# testSensor.net
KiCad netlist of a schematic drawn in Altium Designer
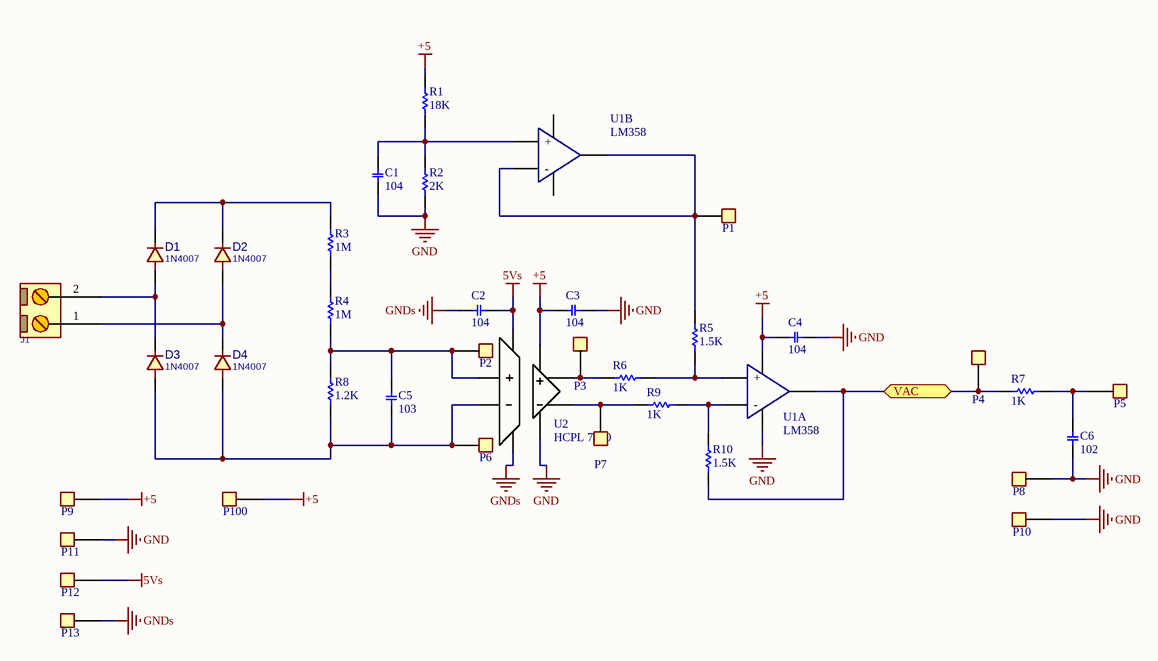
[diagram p0: testSensor.SchDoc]

(export (version "E")
  (design (tool "Eeschema 10.0.6"))
  (components
    (comp (ref "C1")
      (value "104")
      (footprint "CAP 104")
      (description "CAP Keo")
      (fields (field (name "COPYRIGHT") "VanDungEvn"))
      (libsource (lib "IoT") (part "CAP Keo"))
    )
    (comp (ref "C2")
      (value "104")
      (footprint "CAP 104")
      (description "CAP Keo")
      (fields (field (name "COPYRIGHT") "VanDungEvn"))
      (libsource (lib "IoT") (part "CAP Keo"))
    )
    (comp (ref "C3")
      (value "104")
      (footprint "CAP 104")
      (description "CAP Keo")
      (fields (field (name "COPYRIGHT") "VanDungEvn"))
      (libsource (lib "IoT") (part "CAP Keo"))
    )
    (comp (ref "C4")
      (value "104")
      (footprint "CAP 104")
      (description "CAP Keo")
      (fields (field (name "COPYRIGHT") "VanDungEvn"))
      (libsource (lib "IoT") (part "CAP Keo"))
    )
    (comp (ref "C5")
      (value "103")
      (footprint "CAP 104")
      (description "CAP Keo")
      (fields (field (name "COPYRIGHT") "VanDungEvn"))
      (libsource (lib "IoT") (part "CAP Keo"))
    )
    (comp (ref "C6")
      (value "102")
      (footprint "CAP 104")
      (description "CAP Keo")
      (fields (field (name "COPYRIGHT") "VanDungEvn"))
      (libsource (lib "IoT") (part "CAP Keo"))
    )
    (comp (ref "D1")
      (value "1N4007")
      (footprint "1N4007")
      (description "DIODE DIP")
      (fields (field (name "MANF") "Kingtronics") (field (name "MANF_P#") "M7"))
      (libsource (lib "IoT") (part "DIODE DIP"))
    )
    (comp (ref "D2")
      (value "1N4007")
      (footprint "1N4007")
      (description "DIODE DIP")
      (fields (field (name "MANF") "Kingtronics") (field (name "MANF_P#") "M7"))
      (libsource (lib "IoT") (part "DIODE DIP"))
    )
    (comp (ref "D3")
      (value "1N4007")
      (footprint "1N4007")
      (description "DIODE DIP")
      (fields (field (name "MANF") "Kingtronics") (field (name "MANF_P#") "M7"))
      (libsource (lib "IoT") (part "DIODE DIP"))
    )
    (comp (ref "D4")
      (value "1N4007")
      (footprint "1N4007")
      (description "DIODE DIP")
      (fields (field (name "MANF") "Kingtronics") (field (name "MANF_P#") "M7"))
      (libsource (lib "IoT") (part "DIODE DIP"))
    )
    (comp (ref "J1")
      (value "CONN_TB2")
      (footprint "TBG_2")
      (description "CONN, TERMINAL BLOCK, 5.08mm pitch")
      (libsource (lib "IoT") (part "CONN_TB2"))
    )
    (comp (ref "P1")
      (value "test PCB")
      (footprint "tp_red_1p")
      (description "testpin")
      (libsource (lib "") (part "test PCB_1"))
    )
    (comp (ref "P2")
      (value "test PCB")
      (footprint "tp_red_1p")
      (description "testpin")
      (libsource (lib "") (part "test PCB_1"))
    )
    (comp (ref "P3")
      (value "test PCB")
      (footprint "tp_red_1p")
      (description "testpin")
      (libsource (lib "") (part "test PCB_2"))
    )
    (comp (ref "P4")
      (value "test PCB")
      (footprint "tp_red_1p")
      (description "testpin")
      (libsource (lib "") (part "test PCB_2"))
    )
    (comp (ref "P5")
      (value "test PCB")
      (footprint "tp_red_1p")
      (description "testpin")
      (libsource (lib "") (part "test PCB_1"))
    )
    (comp (ref "P6")
      (value "test PCB")
      (footprint "Tp_black_1p")
      (description "testpin")
      (libsource (lib "") (part "test PCB_1"))
    )
    (comp (ref "P7")
      (value "test PCB")
      (footprint "Tp_black_1p")
      (description "testpin")
      (libsource (lib "") (part "test PCB_3"))
    )
    (comp (ref "P8")
      (value "test PCB")
      (footprint "Tp_black_1p")
      (description "testpin")
      (libsource (lib "IoT") (part "test PCB"))
    )
    (comp (ref "P9")
      (value "test PCB")
      (footprint "tp_red_1p")
      (description "testpin")
      (libsource (lib "IoT") (part "test PCB"))
    )
    (comp (ref "P10")
      (value "test PCB")
      (footprint "Tp_black_1p")
      (description "testpin")
      (libsource (lib "IoT") (part "test PCB"))
    )
    (comp (ref "P11")
      (value "test PCB")
      (footprint "Tp_black_1p")
      (description "testpin")
      (libsource (lib "IoT") (part "test PCB"))
    )
    (comp (ref "P12")
      (value "test PCB")
      (footprint "tp_red_1p")
      (description "testpin")
      (libsource (lib "IoT") (part "test PCB"))
    )
    (comp (ref "P13")
      (value "test PCB")
      (footprint "Tp_black_1p")
      (description "testpin")
      (libsource (lib "IoT") (part "test PCB"))
    )
    (comp (ref "P100")
      (value "test PCB")
      (footprint "tp_red_1p")
      (description "testpin")
      (libsource (lib "IoT") (part "test PCB"))
    )
    (comp (ref "R1")
      (value "18K")
      (footprint "R1/4W4")
      (description "RES DIP")
      (libsource (lib "IoT") (part "RES DIP"))
    )
    (comp (ref "R2")
      (value "2K")
      (footprint "R1/4W4")
      (description "RES DIP")
      (libsource (lib "IoT") (part "RES DIP"))
    )
    (comp (ref "R3")
      (value "1M")
      (footprint "R1/4W4")
      (description "RES DIP")
      (libsource (lib "IoT") (part "RES DIP"))
    )
    (comp (ref "R4")
      (value "1M")
      (footprint "R1/4W4")
      (description "RES DIP")
      (libsource (lib "IoT") (part "RES DIP"))
    )
    (comp (ref "R5")
      (value "1.5K")
      (footprint "R1/4W4")
      (description "RES DIP")
      (libsource (lib "IoT") (part "RES DIP"))
    )
    (comp (ref "R6")
      (value "1K")
      (footprint "R1/4W4")
      (description "RES DIP")
      (libsource (lib "IoT") (part "RES DIP"))
    )
    (comp (ref "R7")
      (value "1K")
      (footprint "R1/4W4")
      (description "RES DIP")
      (libsource (lib "IoT") (part "RES DIP"))
    )
    (comp (ref "R8")
      (value "1.2K")
      (footprint "R1/4W4")
      (description "RES DIP")
      (libsource (lib "IoT") (part "RES DIP"))
    )
    (comp (ref "R9")
      (value "1K")
      (footprint "R1/4W4")
      (description "RES DIP")
      (libsource (lib "IoT") (part "RES DIP"))
    )
    (comp (ref "R10")
      (value "1.5K")
      (footprint "R1/4W4")
      (description "RES DIP")
      (libsource (lib "IoT") (part "RES DIP"))
    )
    (comp (ref "U1")
      (value "LM358")
      (footprint "DIP-8_2.54_8_t/h")
      (description "LM358 Dual Opamp")
      (libsource (lib "IoT") (part "LM358"))
    )
    (comp (ref "U2")
      (value "HCPL 7800")
      (footprint "SOP-8P")
      (description "HCPL 7800 Isolation Amplifer, Opamp")
      (libsource (lib "IoT") (part "HCPL 7800"))
    )
  )
  (nets
    (net (code "1") (name "+5") (class "Default")
      (node (ref "C3") (pin "1") (pinfunction "1_1") (pintype "passive"))
      (node (ref "C4") (pin "1") (pinfunction "1_1") (pintype "passive"))
      (node (ref "P100") (pin "1") (pinfunction "1_1") (pintype "power_in"))
      (node (ref "P9") (pin "1") (pinfunction "1_1") (pintype "power_in"))
      (node (ref "R1") (pin "2") (pinfunction "2_2") (pintype "passive"))
      (node (ref "U1") (pin "8") (pinfunction "VCC_8") (pintype "passive"))
      (node (ref "U2") (pin "8") (pinfunction "VDD2_8") (pintype "passive"))
    )
    (net (code "2") (name "/VAC") (class "Default")
      (node (ref "P4") (pin "1") (pinfunction "1_1") (pintype "power_in"))
      (node (ref "R10") (pin "1") (pinfunction "1_1") (pintype "passive"))
      (node (ref "R7") (pin "2") (pinfunction "2_2") (pintype "passive"))
      (node (ref "U1") (pin "1") (pinfunction "OUT1_1") (pintype "passive"))
    )
    (net (code "3") (name "5Vs") (class "Default")
      (node (ref "C2") (pin "2") (pinfunction "2_2") (pintype "passive"))
      (node (ref "P12") (pin "1") (pinfunction "1_1") (pintype "power_in"))
      (node (ref "U2") (pin "1") (pinfunction "VDD1_1") (pintype "passive"))
    )
    (net (code "4") (name "GND") (class "Default")
      (node (ref "C1") (pin "1") (pinfunction "1_1") (pintype "passive"))
      (node (ref "C3") (pin "2") (pinfunction "2_2") (pintype "passive"))
      (node (ref "C4") (pin "2") (pinfunction "2_2") (pintype "passive"))
      (node (ref "C6") (pin "1") (pinfunction "1_1") (pintype "passive"))
      (node (ref "P10") (pin "1") (pinfunction "1_1") (pintype "power_in"))
      (node (ref "P11") (pin "1") (pinfunction "1_1") (pintype "power_in"))
      (node (ref "P8") (pin "1") (pinfunction "1_1") (pintype "power_in"))
      (node (ref "R2") (pin "1") (pinfunction "1_1") (pintype "passive"))
      (node (ref "U1") (pin "4") (pinfunction "GND_4") (pintype "passive"))
      (node (ref "U2") (pin "5") (pinfunction "GND2_5") (pintype "passive"))
    )
    (net (code "5") (name "GNDs") (class "Default")
      (node (ref "C2") (pin "1") (pinfunction "1_1") (pintype "passive"))
      (node (ref "P13") (pin "1") (pinfunction "1_1") (pintype "power_in"))
      (node (ref "U2") (pin "4") (pinfunction "GND1_4") (pintype "passive"))
    )
    (net (code "6") (name "Net-(C5-Pad1)") (class "Default")
      (node (ref "C5") (pin "1") (pinfunction "1_1") (pintype "passive"))
      (node (ref "D3") (pin "1") (pinfunction "1_1") (pintype "passive"))
      (node (ref "D4") (pin "1") (pinfunction "1_1") (pintype "passive"))
      (node (ref "P6") (pin "1") (pinfunction "1_1") (pintype "power_in"))
      (node (ref "R8") (pin "1") (pinfunction "1_1") (pintype "passive"))
      (node (ref "U2") (pin "3") (pinfunction "-_3") (pintype "passive"))
    )
    (net (code "7") (name "Net-(C5-Pad2)") (class "Default")
      (node (ref "C5") (pin "2") (pinfunction "2_2") (pintype "passive"))
      (node (ref "P2") (pin "1") (pinfunction "1_1") (pintype "power_in"))
      (node (ref "R4") (pin "1") (pinfunction "1_1") (pintype "passive"))
      (node (ref "R8") (pin "2") (pinfunction "2_2") (pintype "passive"))
      (node (ref "U2") (pin "2") (pinfunction "+_2") (pintype "passive"))
    )
    (net (code "8") (name "Net-(C6-Pad2)") (class "Default")
      (node (ref "C6") (pin "2") (pinfunction "2_2") (pintype "passive"))
      (node (ref "P5") (pin "1") (pinfunction "1_1") (pintype "power_in"))
      (node (ref "R7") (pin "1") (pinfunction "1_1") (pintype "passive"))
    )
    (net (code "9") (name "Net-(D1-Pad1)") (class "Default")
      (node (ref "D1") (pin "1") (pinfunction "1_1") (pintype "passive"))
      (node (ref "D3") (pin "2") (pinfunction "2_2") (pintype "passive"))
      (node (ref "J1") (pin "2") (pinfunction "2_2") (pintype "passive"))
    )
    (net (code "10") (name "Net-(D1-Pad2)") (class "Default")
      (node (ref "D1") (pin "2") (pinfunction "2_2") (pintype "passive"))
      (node (ref "D2") (pin "2") (pinfunction "2_2") (pintype "passive"))
      (node (ref "R3") (pin "2") (pinfunction "2_2") (pintype "passive"))
    )
    (net (code "11") (name "Net-(D2-Pad1)") (class "Default")
      (node (ref "D2") (pin "1") (pinfunction "1_1") (pintype "passive"))
      (node (ref "D4") (pin "2") (pinfunction "2_2") (pintype "passive"))
      (node (ref "J1") (pin "1") (pinfunction "1_1") (pintype "passive"))
    )
    (net (code "12") (name "Net-(P3-Pad1)") (class "Default")
      (node (ref "P3") (pin "1") (pinfunction "1_1") (pintype "power_in"))
      (node (ref "R6") (pin "2") (pinfunction "2_2") (pintype "passive"))
      (node (ref "U2") (pin "7") (pinfunction "+_7") (pintype "passive"))
    )
    (net (code "13") (name "Net-(P7-Pad1)") (class "Default")
      (node (ref "P7") (pin "1") (pinfunction "1_1") (pintype "power_in"))
      (node (ref "R9") (pin "2") (pinfunction "2_2") (pintype "passive"))
      (node (ref "U2") (pin "6") (pinfunction "-_6") (pintype "passive"))
    )
    (net (code "14") (name "Net-(R3-Pad1)") (class "Default")
      (node (ref "R3") (pin "1") (pinfunction "1_1") (pintype "passive"))
      (node (ref "R4") (pin "2") (pinfunction "2_2") (pintype "passive"))
    )
    (net (code "15") (name "Net-(U1A-+)") (class "Default")
      (node (ref "R5") (pin "1") (pinfunction "1_1") (pintype "passive"))
      (node (ref "R6") (pin "1") (pinfunction "1_1") (pintype "passive"))
      (node (ref "U1") (pin "3") (pinfunction "+_3") (pintype "passive"))
    )
    (net (code "16") (name "Net-(U1A--)") (class "Default")
      (node (ref "R10") (pin "2") (pinfunction "2_2") (pintype "passive"))
      (node (ref "R9") (pin "1") (pinfunction "1_1") (pintype "passive"))
      (node (ref "U1") (pin "2") (pinfunction "-_2") (pintype "passive"))
    )
    (net (code "17") (name "Net-(U1B-+)") (class "Default")
      (node (ref "C1") (pin "2") (pinfunction "2_2") (pintype "passive"))
      (node (ref "R1") (pin "1") (pinfunction "1_1") (pintype "passive"))
      (node (ref "R2") (pin "2") (pinfunction "2_2") (pintype "passive"))
      (node (ref "U1") (pin "5") (pinfunction "+_5") (pintype "passive"))
    )
    (net (code "18") (name "Net-(U1B--)") (class "Default")
      (node (ref "P1") (pin "1") (pinfunction "1_1") (pintype "power_in"))
      (node (ref "R5") (pin "2") (pinfunction "2_2") (pintype "passive"))
      (node (ref "U1") (pin "6") (pinfunction "-_6") (pintype "passive"))
      (node (ref "U1") (pin "7") (pinfunction "OUT2_7") (pintype "passive"))
    )
    (net (code "19") (name "unconnected-(U1B-GND-Pad4)") (class "Default")
      (node (ref "U1") (pin "4") (pinfunction "GND_4") (pintype "passive"))
    )
    (net (code "20") (name "unconnected-(U1B-VCC-Pad8)") (class "Default")
      (node (ref "U1") (pin "8") (pinfunction "VCC_8") (pintype "passive"))
    )
  )
)
